# rev1.net
KiCad netlist of a schematic drawn in EAGLE
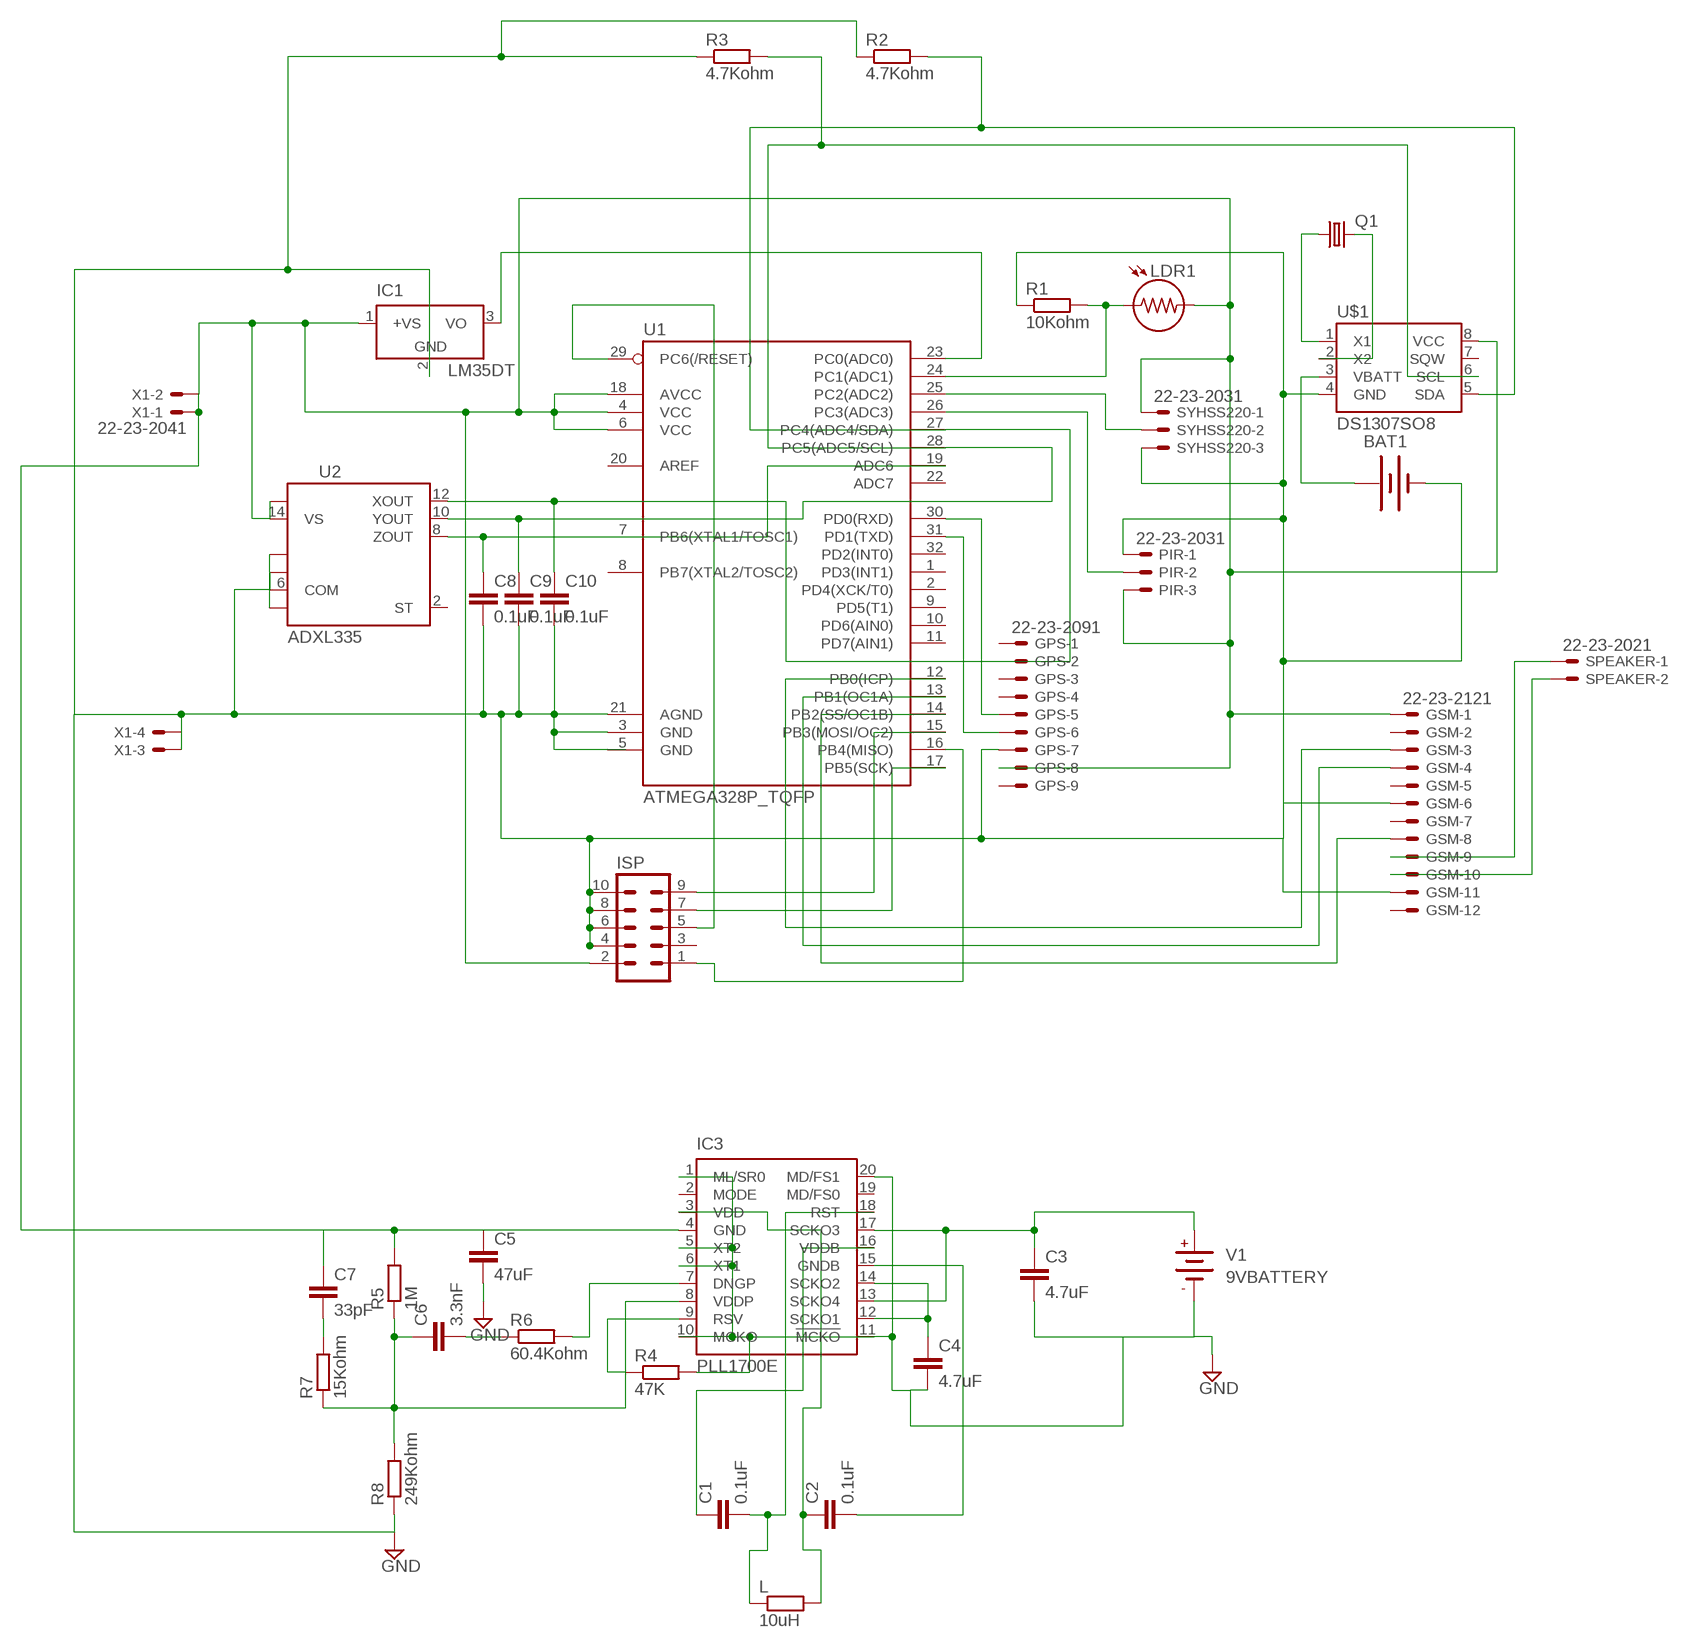
[diagram p0: schematic, sheet 1]

(export (version "E")
  (design (tool "Eeschema 10.0.6"))
  (components
    (comp (ref "BAT1")
      (value "BATTERY20PTH")
      (footprint "eagle-import:BATTCOM_20MM_PTH")
      (libsource (lib "eagle-import") (part "BATTERY20PTH"))
    )
    (comp (ref "C1")
      (value "0.1uF")
      (footprint "eagle-import:0402-CAP")
      (libsource (lib "eagle-import") (part "0.1UF-16V(+-10%)(0402)"))
    )
    (comp (ref "C2")
      (value "0.1uF")
      (footprint "eagle-import:0402-CAP")
      (libsource (lib "eagle-import") (part "0.1UF-16V(+-10%)(0402)"))
    )
    (comp (ref "C3")
      (value "4.7uF")
      (footprint "eagle-import:0603-CAP")
      (libsource (lib "eagle-import") (part "4.7UF-6.3V-10%(0603)0603"))
    )
    (comp (ref "C4")
      (value "4.7uF")
      (footprint "eagle-import:0603-CAP")
      (libsource (lib "eagle-import") (part "4.7UF-6.3V-10%(0603)0603"))
    )
    (comp (ref "C5")
      (value "47uF")
      (footprint "eagle-import:0603-CAP")
      (libsource (lib "eagle-import") (part "CAP0603-CAP"))
    )
    (comp (ref "C6")
      (value "3.3nF")
      (footprint "eagle-import:0603-CAP")
      (libsource (lib "eagle-import") (part "3.3NF-100V-10%(0603)"))
    )
    (comp (ref "C7")
      (value "33pF")
      (footprint "eagle-import:0603-CAP")
      (libsource (lib "eagle-import") (part "33PF-50V-5%-(0603)"))
    )
    (comp (ref "C8")
      (value "0.1uF")
      (footprint "eagle-import:0402-CAP")
      (libsource (lib "eagle-import") (part "0.1UF-16V(+-10%)(0402)"))
    )
    (comp (ref "C9")
      (value "0.1uF")
      (footprint "eagle-import:0402-CAP")
      (libsource (lib "eagle-import") (part "0.1UF-16V(+-10%)(0402)"))
    )
    (comp (ref "C10")
      (value "0.1uF")
      (footprint "eagle-import:0402-CAP")
      (libsource (lib "eagle-import") (part "0.1UF-16V(+-10%)(0402)"))
    )
    (comp (ref "GPS")
      (value "22-23-2091")
      (footprint "eagle-import:22-23-2091")
      (fields (field (name "MF") "MOLEX"))
      (libsource (lib "eagle-import") (part "22-23-2091"))
    )
    (comp (ref "GSM")
      (value "22-23-2121")
      (footprint "eagle-import:22-23-2121")
      (fields (field (name "MF") "MOLEX"))
      (libsource (lib "eagle-import") (part "22-23-2121"))
    )
    (comp (ref "IC1")
      (value "LM35DT")
      (footprint "eagle-import:TO220V")
      (libsource (lib "eagle-import") (part "LM35DT"))
    )
    (comp (ref "IC3")
      (value "PLL1700E")
      (footprint "eagle-import:SSOP20")
      (fields (field (name "MF") "TEXAS INSTRUMENT CONNECTORS"))
      (libsource (lib "eagle-import") (part "PLL1700E"))
    )
    (comp (ref "ISP")
      (value "ML10")
      (footprint "eagle-import:ML10")
      (libsource (lib "eagle-import") (part "ML10"))
    )
    (comp (ref "L")
      (value "10uH")
      (footprint "eagle-import:R0207_4")
      (libsource (lib "eagle-import") (part "6MM-EU4"))
    )
    (comp (ref "LDR1")
      (value "LDR5MM")
      (footprint "eagle-import:LDR338-54C")
      (libsource (lib "eagle-import") (part "LDR5MM"))
    )
    (comp (ref "PIR")
      (value "22-23-2031")
      (footprint "eagle-import:22-23-2031")
      (fields (field (name "MF") "MOLEX"))
      (libsource (lib "eagle-import") (part "22-23-2031"))
    )
    (comp (ref "Q1")
      (value "CRYSTALTC26H")
      (footprint "eagle-import:TC26H")
      (libsource (lib "eagle-import") (part "CRYSTALTC26H"))
    )
    (comp (ref "R1")
      (value "10Kohm")
      (footprint "eagle-import:M1206")
      (libsource (lib "eagle-import") (part "R-EU_M1206"))
    )
    (comp (ref "R2")
      (value "4.7Kohm")
      (footprint "eagle-import:M1206")
      (libsource (lib "eagle-import") (part "R-EU_M1206"))
    )
    (comp (ref "R3")
      (value "4.7Kohm")
      (footprint "eagle-import:M1206")
      (libsource (lib "eagle-import") (part "R-EU_M1206"))
    )
    (comp (ref "R4")
      (value "47K")
      (footprint "eagle-import:M3216")
      (libsource (lib "eagle-import") (part "R-EU_M3216"))
    )
    (comp (ref "R5")
      (value "1M")
      (footprint "eagle-import:M3216")
      (libsource (lib "eagle-import") (part "R-EU_M3216"))
    )
    (comp (ref "R6")
      (value "60.4Kohm")
      (footprint "eagle-import:M3216")
      (libsource (lib "eagle-import") (part "R-EU_M3216"))
    )
    (comp (ref "R7")
      (value "15Kohm")
      (footprint "eagle-import:M1206")
      (libsource (lib "eagle-import") (part "R-EU_M1206"))
    )
    (comp (ref "R8")
      (value "249Kohm")
      (footprint "eagle-import:M1206")
      (libsource (lib "eagle-import") (part "R-EU_M1206"))
    )
    (comp (ref "SPEAKER")
      (value "22-23-2021")
      (footprint "eagle-import:22-23-2021")
      (fields (field (name "MF") "MOLEX"))
      (libsource (lib "eagle-import") (part "22-23-2021"))
    )
    (comp (ref "SYHSS220")
      (value "22-23-2031")
      (footprint "eagle-import:22-23-2031")
      (fields (field (name "MF") "MOLEX"))
      (libsource (lib "eagle-import") (part "22-23-2031"))
    )
    (comp (ref "U$1")
      (value "DS1307SO8")
      (footprint "eagle-import:SO08")
      (libsource (lib "eagle-import") (part "DS1307SO8"))
    )
    (comp (ref "U1")
      (value "ATMEGA328P_TQFP")
      (footprint "eagle-import:TQFP32-08")
      (libsource (lib "eagle-import") (part "ATMEGA328P_TQFP"))
    )
    (comp (ref "U2")
      (value "ADXL335")
      (footprint "eagle-import:LFCSP-16")
      (libsource (lib "eagle-import") (part "ADXL335"))
    )
    (comp (ref "V1")
      (value "9VBATTERY")
      (footprint "eagle-import:AB9V")
      (libsource (lib "eagle-import") (part "9VBATTERY"))
    )
    (comp (ref "X1")
      (value "22-23-2041")
      (footprint "eagle-import:22-23-2041")
      (fields (field (name "MF") "MOLEX"))
      (libsource (lib "eagle-import") (part "22-23-2041"))
    )
  )
  (nets
    (net (code "1") (name "GND") (class "Default")
      (node (ref "BAT1") (pin "2") (pinfunction "-_2") (pintype "power_in"))
      (node (ref "C10") (pin "2") (pinfunction "2_2") (pintype "passive"))
      (node (ref "C3") (pin "2") (pinfunction "2_2") (pintype "passive"))
      (node (ref "C4") (pin "2") (pinfunction "2_2") (pintype "passive"))
      (node (ref "C5") (pin "2") (pinfunction "2_2") (pintype "passive"))
      (node (ref "C8") (pin "2") (pinfunction "2_2") (pintype "passive"))
      (node (ref "C9") (pin "2") (pinfunction "2_2") (pintype "passive"))
      (node (ref "GPS") (pin "7") (pinfunction "S_7") (pintype "passive"))
      (node (ref "GSM") (pin "11") (pinfunction "S_11") (pintype "passive"))
      (node (ref "GSM") (pin "6") (pinfunction "S_6") (pintype "passive"))
      (node (ref "IC1") (pin "2") (pinfunction "GND_2") (pintype "power_in"))
      (node (ref "IC3") (pin "1") (pinfunction "ML/SR0_1") (pintype "input"))
      (node (ref "IC3") (pin "10") (pinfunction "MCKO_10") (pintype "output"))
      (node (ref "IC3") (pin "11") (pinfunction "~{MCKO}_11") (pintype "output"))
      (node (ref "IC3") (pin "20") (pinfunction "MD/FS1_20") (pintype "input"))
      (node (ref "IC3") (pin "5") (pinfunction "XT2_5") (pintype "input"))
      (node (ref "IC3") (pin "6") (pinfunction "XT1_6") (pintype "input"))
      (node (ref "ISP") (pin "10") (pinfunction "10_10") (pintype "passive"))
      (node (ref "ISP") (pin "4") (pinfunction "4_4") (pintype "passive"))
      (node (ref "ISP") (pin "6") (pinfunction "6_6") (pintype "passive"))
      (node (ref "ISP") (pin "8") (pinfunction "8_8") (pintype "passive"))
      (node (ref "PIR") (pin "1") (pinfunction "S_1") (pintype "passive"))
      (node (ref "R1") (pin "1") (pinfunction "1_1") (pintype "passive"))
      (node (ref "R2") (pin "1") (pinfunction "1_1") (pintype "passive"))
      (node (ref "R3") (pin "1") (pinfunction "1_1") (pintype "passive"))
      (node (ref "R4") (pin "2") (pinfunction "2_2") (pintype "passive"))
      (node (ref "R8") (pin "1") (pinfunction "1_1") (pintype "passive"))
      (node (ref "SYHSS220") (pin "3") (pinfunction "S_3") (pintype "passive"))
      (node (ref "U$1") (pin "4") (pinfunction "GND_4") (pintype "bidirectional"))
      (node (ref "U1") (pin "21") (pinfunction "AGND_21") (pintype "bidirectional"))
      (node (ref "U1") (pin "3") (pinfunction "GND_3") (pintype "bidirectional"))
      (node (ref "U2") (pin "3") (pinfunction "COM_3") (pintype "bidirectional"))
      (node (ref "U2") (pin "5") (pinfunction "COM_5") (pintype "bidirectional"))
      (node (ref "U2") (pin "6") (pinfunction "COM_6") (pintype "bidirectional"))
      (node (ref "U2") (pin "7") (pinfunction "COM_7") (pintype "bidirectional"))
      (node (ref "V1") (pin "-") (pinfunction "-_-") (pintype "passive"))
      (node (ref "X1") (pin "3") (pinfunction "S_3") (pintype "passive"))
      (node (ref "X1") (pin "4") (pinfunction "S_4") (pintype "passive"))
    )
    (net (code "2") (name "Net-(BAT1-+)") (class "Default")
      (node (ref "BAT1") (pin "1") (pinfunction "+_1") (pintype "power_in"))
      (node (ref "U$1") (pin "3") (pinfunction "VBATT_3") (pintype "bidirectional"))
    )
    (net (code "3") (name "Net-(C6-Pad2)") (class "Default")
      (node (ref "C6") (pin "2") (pinfunction "2_2") (pintype "passive"))
      (node (ref "R6") (pin "1") (pinfunction "1_1") (pintype "passive"))
    )
    (net (code "4") (name "Net-(C7-Pad2)") (class "Default")
      (node (ref "C7") (pin "2") (pinfunction "2_2") (pintype "passive"))
      (node (ref "R7") (pin "2") (pinfunction "2_2") (pintype "passive"))
    )
    (net (code "5") (name "Net-(GPSE-S)") (class "Default")
      (node (ref "GPS") (pin "5") (pinfunction "S_5") (pintype "passive"))
      (node (ref "U1") (pin "30") (pinfunction "PD0(RXD)_30") (pintype "bidirectional"))
    )
    (net (code "6") (name "Net-(GPSF-S)") (class "Default")
      (node (ref "GPS") (pin "6") (pinfunction "S_6") (pintype "passive"))
      (node (ref "U1") (pin "31") (pinfunction "PD1(TXD)_31") (pintype "bidirectional"))
    )
    (net (code "7") (name "Net-(GPSH-S)") (class "Default")
      (node (ref "C5") (pin "1") (pinfunction "1_1") (pintype "passive"))
      (node (ref "C7") (pin "1") (pinfunction "1_1") (pintype "passive"))
      (node (ref "GPS") (pin "8") (pinfunction "S_8") (pintype "passive"))
      (node (ref "GSM") (pin "1") (pinfunction "S_1") (pintype "passive"))
      (node (ref "IC1") (pin "1") (pinfunction "+VS_1") (pintype "input"))
      (node (ref "IC3") (pin "4") (pinfunction "GND_4") (pintype "power_in"))
      (node (ref "ISP") (pin "2") (pinfunction "2_2") (pintype "passive"))
      (node (ref "LDR1") (pin "2") (pinfunction "2_2") (pintype "passive"))
      (node (ref "PIR") (pin "3") (pinfunction "S_3") (pintype "passive"))
      (node (ref "R5") (pin "2") (pinfunction "2_2") (pintype "passive"))
      (node (ref "SYHSS220") (pin "1") (pinfunction "S_1") (pintype "passive"))
      (node (ref "U$1") (pin "8") (pinfunction "VCC_8") (pintype "bidirectional"))
      (node (ref "U1") (pin "18") (pinfunction "AVCC_18") (pintype "bidirectional"))
      (node (ref "U1") (pin "4") (pinfunction "VCC_4") (pintype "bidirectional"))
      (node (ref "U1") (pin "6") (pinfunction "VCC_6") (pintype "bidirectional"))
      (node (ref "U2") (pin "14") (pinfunction "VS_14") (pintype "bidirectional"))
      (node (ref "U2") (pin "15") (pinfunction "VS_15") (pintype "bidirectional"))
      (node (ref "X1") (pin "1") (pinfunction "S_1") (pintype "passive"))
      (node (ref "X1") (pin "2") (pinfunction "S_2") (pintype "passive"))
    )
    (net (code "8") (name "Net-(GSMB-S)") (class "Default")
      (node (ref "GSM") (pin "10") (pinfunction "S_10") (pintype "passive"))
      (node (ref "SPEAKER") (pin "2") (pinfunction "S_2") (pintype "passive"))
    )
    (net (code "9") (name "Net-(GSMF-S)") (class "Default")
      (node (ref "GSM") (pin "3") (pinfunction "S_3") (pintype "passive"))
      (node (ref "U1") (pin "12") (pinfunction "PB0(ICP)_12") (pintype "bidirectional"))
    )
    (net (code "10") (name "Net-(GSMG-S)") (class "Default")
      (node (ref "GSM") (pin "4") (pinfunction "S_4") (pintype "passive"))
      (node (ref "U1") (pin "13") (pinfunction "PB1(OC1A)_13") (pintype "bidirectional"))
    )
    (net (code "11") (name "Net-(GSMK-S)") (class "Default")
      (node (ref "GSM") (pin "8") (pinfunction "S_8") (pintype "passive"))
      (node (ref "U1") (pin "14") (pinfunction "PB2(SS/OC1B)_14") (pintype "bidirectional"))
    )
    (net (code "12") (name "Net-(GSML-S)") (class "Default")
      (node (ref "GSM") (pin "9") (pinfunction "S_9") (pintype "passive"))
      (node (ref "SPEAKER") (pin "1") (pinfunction "S_1") (pintype "passive"))
    )
    (net (code "13") (name "Net-(IC1-VO)") (class "Default")
      (node (ref "IC1") (pin "3") (pinfunction "VO_3") (pintype "input"))
      (node (ref "U1") (pin "23") (pinfunction "PC0(ADC0)_23") (pintype "bidirectional"))
    )
    (net (code "14") (name "Net-(IC3-DNGP)") (class "Default")
      (node (ref "IC3") (pin "7") (pinfunction "DNGP_7") (pintype "power_in"))
      (node (ref "R6") (pin "2") (pinfunction "2_2") (pintype "passive"))
    )
    (net (code "15") (name "Net-(IC3-GNDB)") (class "Default")
      (node (ref "C2") (pin "2") (pinfunction "2_2") (pintype "passive"))
      (node (ref "IC3") (pin "15") (pinfunction "GNDB_15") (pintype "power_in"))
    )
    (net (code "16") (name "Net-(IC3-RST)") (class "Default")
      (node (ref "C1") (pin "2") (pinfunction "2_2") (pintype "passive"))
      (node (ref "IC3") (pin "18") (pinfunction "RST_18") (pintype "input"))
      (node (ref "L") (pin "1") (pinfunction "1_1") (pintype "passive"))
    )
    (net (code "17") (name "Net-(IC3-RSV)") (class "Default")
      (node (ref "IC3") (pin "9") (pinfunction "RSV_9") (pintype "passive"))
      (node (ref "R4") (pin "1") (pinfunction "1_1") (pintype "passive"))
    )
    (net (code "18") (name "Net-(IC3-SCKO1)") (class "Default")
      (node (ref "C4") (pin "1") (pinfunction "1_1") (pintype "passive"))
      (node (ref "IC3") (pin "12") (pinfunction "SCKO1_12") (pintype "output"))
      (node (ref "IC3") (pin "14") (pinfunction "SCKO2_14") (pintype "output"))
    )
    (net (code "19") (name "Net-(IC3-SCKO3)") (class "Default")
      (node (ref "C3") (pin "1") (pinfunction "1_1") (pintype "passive"))
      (node (ref "IC3") (pin "13") (pinfunction "SCKO4_13") (pintype "output"))
      (node (ref "IC3") (pin "17") (pinfunction "SCKO3_17") (pintype "output"))
      (node (ref "V1") (pin "+") (pinfunction "+_+") (pintype "passive"))
    )
    (net (code "20") (name "Net-(IC3-VDD)") (class "Default")
      (node (ref "C2") (pin "1") (pinfunction "1_1") (pintype "passive"))
      (node (ref "IC3") (pin "3") (pinfunction "VDD_3") (pintype "input"))
      (node (ref "L") (pin "2") (pinfunction "2_2") (pintype "passive"))
    )
    (net (code "21") (name "Net-(IC3-VDDB)") (class "Default")
      (node (ref "C1") (pin "1") (pinfunction "1_1") (pintype "passive"))
      (node (ref "IC3") (pin "16") (pinfunction "VDDB_16") (pintype "power_in"))
    )
    (net (code "22") (name "Net-(IC3-VDDP)") (class "Default")
      (node (ref "C6") (pin "1") (pinfunction "1_1") (pintype "passive"))
      (node (ref "IC3") (pin "8") (pinfunction "VDDP_8") (pintype "power_in"))
      (node (ref "R5") (pin "1") (pinfunction "1_1") (pintype "passive"))
      (node (ref "R7") (pin "1") (pinfunction "1_1") (pintype "passive"))
      (node (ref "R8") (pin "2") (pinfunction "2_2") (pintype "passive"))
    )
    (net (code "23") (name "Net-(PIRB-S)") (class "Default")
      (node (ref "PIR") (pin "2") (pinfunction "S_2") (pintype "passive"))
      (node (ref "U1") (pin "26") (pinfunction "PC3(ADC3)_26") (pintype "bidirectional"))
    )
    (net (code "24") (name "Net-(SYHSS220B-S)") (class "Default")
      (node (ref "SYHSS220") (pin "2") (pinfunction "S_2") (pintype "passive"))
      (node (ref "U1") (pin "25") (pinfunction "PC2(ADC2)_25") (pintype "bidirectional"))
    )
    (net (code "25") (name "Net-(U$1-SCL)") (class "Default")
      (node (ref "C9") (pin "1") (pinfunction "1_1") (pintype "passive"))
      (node (ref "R3") (pin "2") (pinfunction "2_2") (pintype "passive"))
      (node (ref "U$1") (pin "6") (pinfunction "SCL_6") (pintype "bidirectional"))
      (node (ref "U1") (pin "28") (pinfunction "PC5(ADC5/SCL)_28") (pintype "bidirectional"))
      (node (ref "U2") (pin "10") (pinfunction "YOUT_10") (pintype "bidirectional"))
    )
    (net (code "26") (name "Net-(U$1-SDA)") (class "Default")
      (node (ref "C10") (pin "1") (pinfunction "1_1") (pintype "passive"))
      (node (ref "R2") (pin "2") (pinfunction "2_2") (pintype "passive"))
      (node (ref "U$1") (pin "5") (pinfunction "SDA_5") (pintype "bidirectional"))
      (node (ref "U1") (pin "27") (pinfunction "PC4(ADC4/SDA)_27") (pintype "bidirectional"))
      (node (ref "U2") (pin "12") (pinfunction "XOUT_12") (pintype "bidirectional"))
    )
    (net (code "27") (name "Net-(U$1-X1)") (class "Default")
      (node (ref "Q1") (pin "1") (pinfunction "1_1") (pintype "passive"))
      (node (ref "U$1") (pin "1") (pinfunction "X1_1") (pintype "bidirectional"))
    )
    (net (code "28") (name "Net-(U$1-X2)") (class "Default")
      (node (ref "Q1") (pin "2") (pinfunction "2_2") (pintype "passive"))
      (node (ref "U$1") (pin "2") (pinfunction "X2_2") (pintype "bidirectional"))
    )
    (net (code "29") (name "Net-(U1-ADC6)") (class "Default")
      (node (ref "C8") (pin "1") (pinfunction "1_1") (pintype "passive"))
      (node (ref "U1") (pin "19") (pinfunction "ADC6_19") (pintype "bidirectional"))
      (node (ref "U2") (pin "8") (pinfunction "ZOUT_8") (pintype "bidirectional"))
    )
    (net (code "30") (name "Net-(U1-PB3(MOSI{slash}OC2))") (class "Default")
      (node (ref "ISP") (pin "9") (pinfunction "9_9") (pintype "passive"))
      (node (ref "U1") (pin "15") (pinfunction "PB3(MOSI/OC2)_15") (pintype "bidirectional"))
    )
    (net (code "31") (name "Net-(U1-PB4(MISO))") (class "Default")
      (node (ref "ISP") (pin "1") (pinfunction "1_1") (pintype "passive"))
      (node (ref "U1") (pin "16") (pinfunction "PB4(MISO)_16") (pintype "bidirectional"))
    )
    (net (code "32") (name "Net-(U1-PB5(SCK))") (class "Default")
      (node (ref "ISP") (pin "7") (pinfunction "7_7") (pintype "passive"))
      (node (ref "U1") (pin "17") (pinfunction "PB5(SCK)_17") (pintype "bidirectional"))
    )
    (net (code "33") (name "Net-(U1-PC1(ADC1))") (class "Default")
      (node (ref "LDR1") (pin "1") (pinfunction "1_1") (pintype "passive"))
      (node (ref "R1") (pin "2") (pinfunction "2_2") (pintype "passive"))
      (node (ref "U1") (pin "24") (pinfunction "PC1(ADC1)_24") (pintype "bidirectional"))
    )
    (net (code "34") (name "Net-(U1-PC6({slash}RESET))") (class "Default")
      (node (ref "ISP") (pin "5") (pinfunction "5_5") (pintype "passive"))
      (node (ref "U1") (pin "29") (pinfunction "PC6(/RESET)_29") (pintype "bidirectional"))
    )
    (net (code "35") (name "unconnected-(GPSA-S-Pad1)") (class "Default")
      (node (ref "GPS") (pin "1") (pinfunction "S_1") (pintype "passive"))
    )
    (net (code "36") (name "unconnected-(GPSB-S-Pad2)") (class "Default")
      (node (ref "GPS") (pin "2") (pinfunction "S_2") (pintype "passive"))
    )
    (net (code "37") (name "unconnected-(GPSC-S-Pad3)") (class "Default")
      (node (ref "GPS") (pin "3") (pinfunction "S_3") (pintype "passive"))
    )
    (net (code "38") (name "unconnected-(GPSD-S-Pad4)") (class "Default")
      (node (ref "GPS") (pin "4") (pinfunction "S_4") (pintype "passive"))
    )
    (net (code "39") (name "unconnected-(GPSI-S-Pad9)") (class "Default")
      (node (ref "GPS") (pin "9") (pinfunction "S_9") (pintype "passive"))
    )
    (net (code "40") (name "unconnected-(GSMD-S-Pad12)") (class "Default")
      (node (ref "GSM") (pin "12") (pinfunction "S_12") (pintype "passive"))
    )
    (net (code "41") (name "unconnected-(GSME-S-Pad2)") (class "Default")
      (node (ref "GSM") (pin "2") (pinfunction "S_2") (pintype "passive"))
    )
    (net (code "42") (name "unconnected-(GSMH-S-Pad5)") (class "Default")
      (node (ref "GSM") (pin "5") (pinfunction "S_5") (pintype "passive"))
    )
    (net (code "43") (name "unconnected-(GSMJ-S-Pad7)") (class "Default")
      (node (ref "GSM") (pin "7") (pinfunction "S_7") (pintype "passive"))
    )
    (net (code "44") (name "unconnected-(IC3-MD{slash}FS0-Pad19)") (class "Default")
      (node (ref "IC3") (pin "19") (pinfunction "MD/FS0_19") (pintype "input"))
    )
    (net (code "45") (name "unconnected-(IC3-MODE-Pad2)") (class "Default")
      (node (ref "IC3") (pin "2") (pinfunction "MODE_2") (pintype "input"))
    )
    (net (code "46") (name "unconnected-(ISP-Pad3)") (class "Default")
      (node (ref "ISP") (pin "3") (pinfunction "3_3") (pintype "passive"))
    )
    (net (code "47") (name "unconnected-(U$1-SQW-Pad7)") (class "Default")
      (node (ref "U$1") (pin "7") (pinfunction "SQW_7") (pintype "bidirectional"))
    )
    (net (code "48") (name "unconnected-(U1-ADC7-Pad22)") (class "Default")
      (node (ref "U1") (pin "22") (pinfunction "ADC7_22") (pintype "bidirectional"))
    )
    (net (code "49") (name "unconnected-(U1-AREF-Pad20)") (class "Default")
      (node (ref "U1") (pin "20") (pinfunction "AREF_20") (pintype "bidirectional"))
    )
    (net (code "50") (name "unconnected-(U1-GND-Pad5)") (class "Default")
      (node (ref "U1") (pin "5") (pinfunction "GND_5") (pintype "bidirectional"))
    )
    (net (code "51") (name "unconnected-(U1-PB6(XTAL1{slash}TOSC1)-Pad7)") (class "Default")
      (node (ref "U1") (pin "7") (pinfunction "PB6(XTAL1/TOSC1)_7") (pintype "bidirectional"))
    )
    (net (code "52") (name "unconnected-(U1-PB7(XTAL2{slash}TOSC2)-Pad8)") (class "Default")
      (node (ref "U1") (pin "8") (pinfunction "PB7(XTAL2/TOSC2)_8") (pintype "bidirectional"))
    )
    (net (code "53") (name "unconnected-(U1-PD2(INT0)-Pad32)") (class "Default")
      (node (ref "U1") (pin "32") (pinfunction "PD2(INT0)_32") (pintype "bidirectional"))
    )
    (net (code "54") (name "unconnected-(U1-PD3(INT1)-Pad1)") (class "Default")
      (node (ref "U1") (pin "1") (pinfunction "PD3(INT1)_1") (pintype "bidirectional"))
    )
    (net (code "55") (name "unconnected-(U1-PD4(XCK{slash}T0)-Pad2)") (class "Default")
      (node (ref "U1") (pin "2") (pinfunction "PD4(XCK/T0)_2") (pintype "bidirectional"))
    )
    (net (code "56") (name "unconnected-(U1-PD5(T1)-Pad9)") (class "Default")
      (node (ref "U1") (pin "9") (pinfunction "PD5(T1)_9") (pintype "bidirectional"))
    )
    (net (code "57") (name "unconnected-(U1-PD6(AIN0)-Pad10)") (class "Default")
      (node (ref "U1") (pin "10") (pinfunction "PD6(AIN0)_10") (pintype "bidirectional"))
    )
    (net (code "58") (name "unconnected-(U1-PD7(AIN1)-Pad11)") (class "Default")
      (node (ref "U1") (pin "11") (pinfunction "PD7(AIN1)_11") (pintype "bidirectional"))
    )
    (net (code "59") (name "unconnected-(U2-ST-Pad2)") (class "Default")
      (node (ref "U2") (pin "2") (pinfunction "ST_2") (pintype "bidirectional"))
    )
  )
)
